# Grove-Barometer_High-Accuracy_v1_0.net
KiCad netlist of a schematic drawn in EAGLE
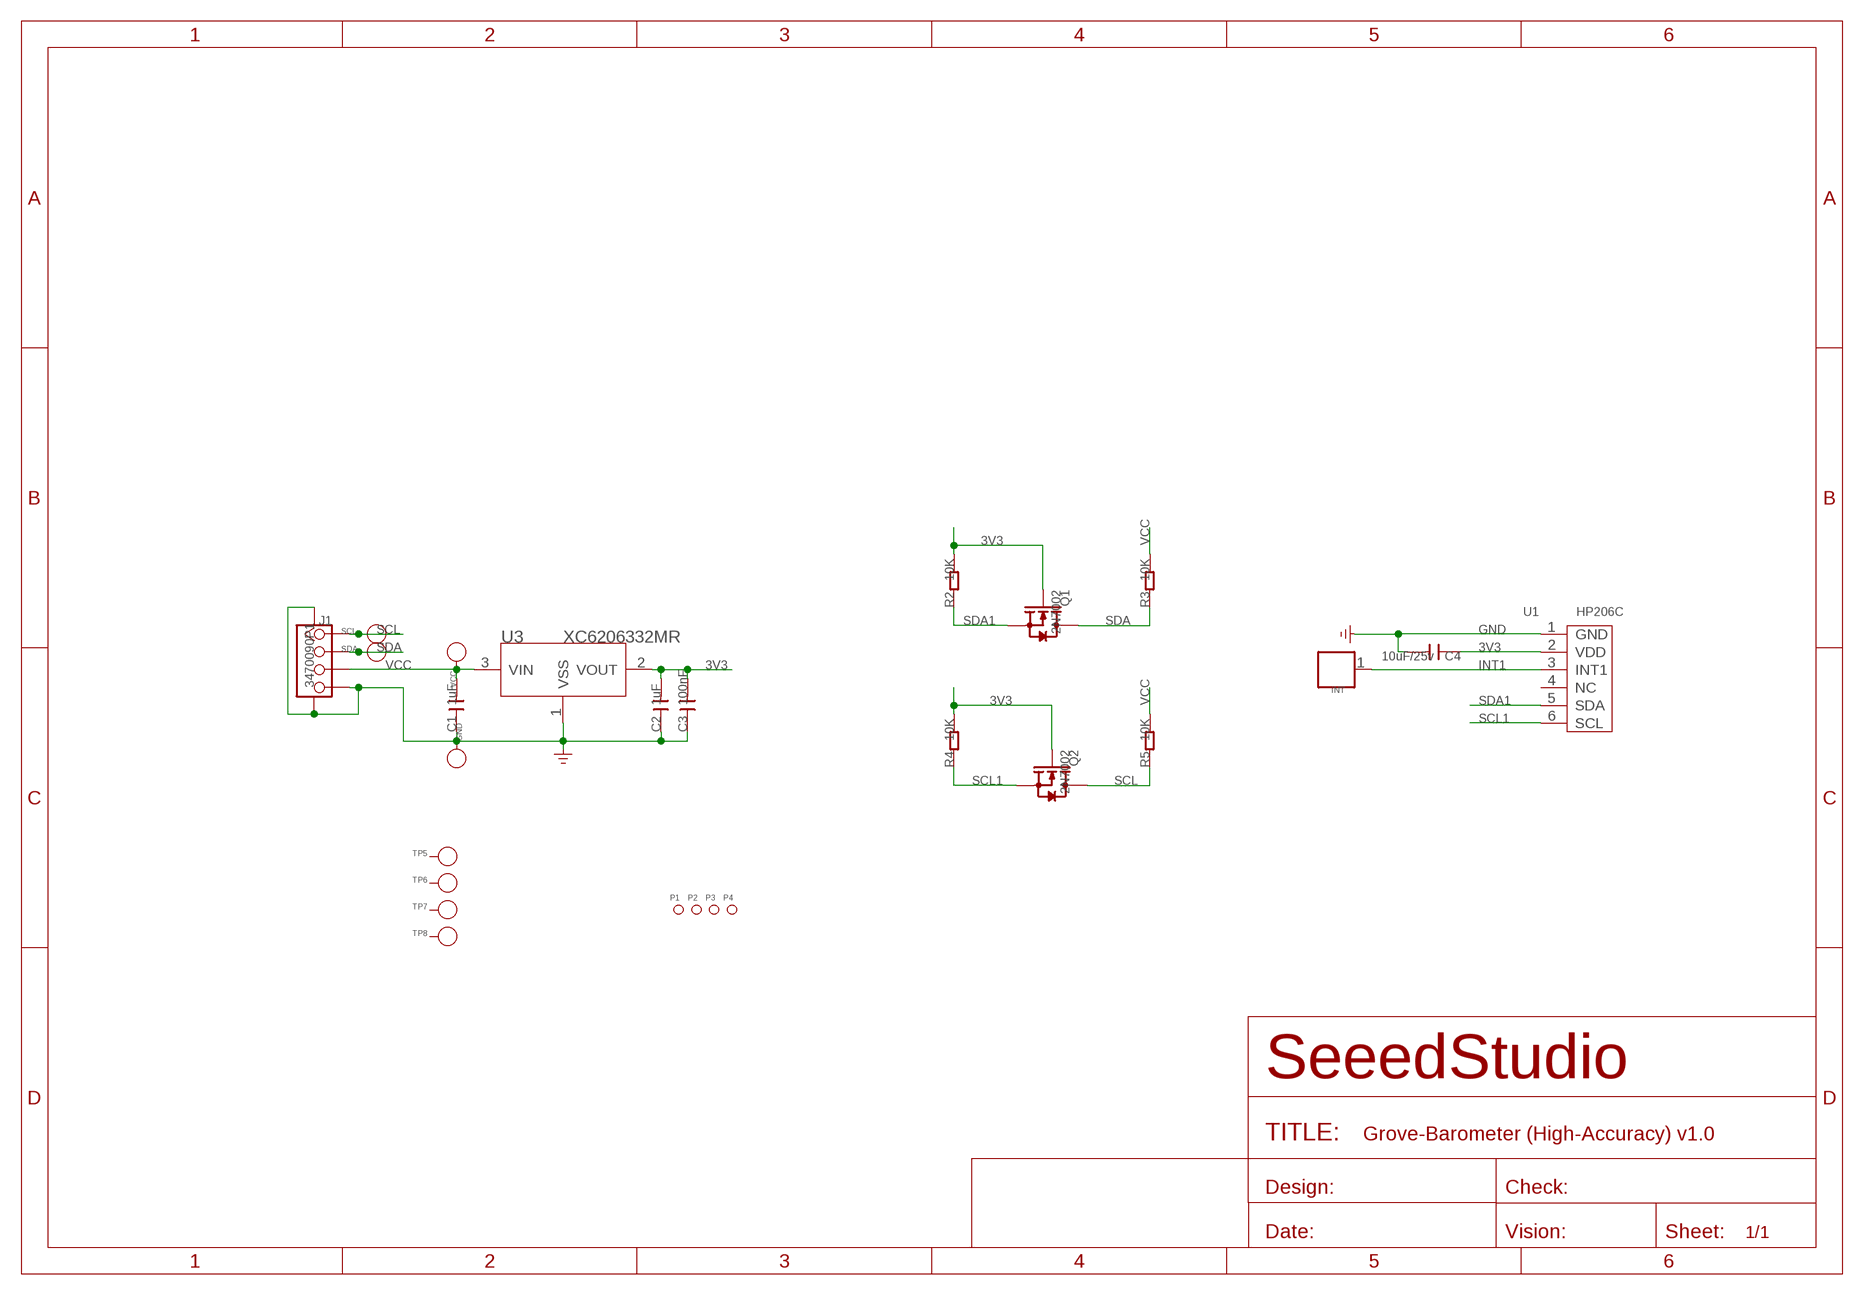
[diagram p0: schematic, sheet 1]

(export (version "E")
  (design (tool "Eeschema 10.0.6"))
  (components
    (comp (ref "C1")
      (value "1uF")
      (footprint "eagle-import:C0603")
      (libsource (lib "eagle-import") (part "C-0603"))
    )
    (comp (ref "C2")
      (value "1uF")
      (footprint "eagle-import:C0603")
      (libsource (lib "eagle-import") (part "C-0603"))
    )
    (comp (ref "C3")
      (value "100nF")
      (footprint "eagle-import:C0603")
      (libsource (lib "eagle-import") (part "C-0603"))
    )
    (comp (ref "C4")
      (value "10uF/25v")
      (footprint "eagle-import:C0805")
      (libsource (lib "eagle-import") (part "C-0805"))
    )
    (comp (ref "GND")
      (value "PAD-TEST-POINT'4545'")
      (footprint "eagle-import:TP_4545")
      (fields (field (name "PARTNO") "DNP"))
      (libsource (lib "eagle-import") (part "PAD-TEST-POINT'4545'"))
    )
    (comp (ref "INT")
      (value "PAD'60/30'")
      (footprint "eagle-import:1P-65_35MIL")
      (libsource (lib "eagle-import") (part "PAD'60/30'"))
    )
    (comp (ref "J1")
      (value "3470090P1")
      (footprint "eagle-import:4P-SMD-2.0")
      (libsource (lib "eagle-import") (part "TWIG-4P-2.0-SMD-FEMALE-REINFORCE'DD'"))
    )
    (comp (ref "P1")
      (value "PAD-MARK")
      (footprint "eagle-import:ROUND-MARK-1.0")
      (fields (field (name "PARTNO") "DNP"))
      (libsource (lib "eagle-import") (part "PAD-MARK"))
    )
    (comp (ref "P2")
      (value "PAD-MARK")
      (footprint "eagle-import:ROUND-MARK-1.0")
      (fields (field (name "PARTNO") "DNP"))
      (libsource (lib "eagle-import") (part "PAD-MARK"))
    )
    (comp (ref "P3")
      (value "PAD-MARK")
      (footprint "eagle-import:ROUND-MARK-1.0")
      (fields (field (name "PARTNO") "DNP"))
      (libsource (lib "eagle-import") (part "PAD-MARK"))
    )
    (comp (ref "P4")
      (value "PAD-MARK")
      (footprint "eagle-import:ROUND-MARK-1.0")
      (fields (field (name "PARTNO") "DNP"))
      (libsource (lib "eagle-import") (part "PAD-MARK"))
    )
    (comp (ref "Q1")
      (value "2N7002")
      (footprint "eagle-import:SOT23")
      (libsource (lib "eagle-import") (part "MOSFET-N'SOT23'"))
    )
    (comp (ref "Q2")
      (value "2N7002")
      (footprint "eagle-import:SOT23")
      (libsource (lib "eagle-import") (part "MOSFET-N'SOT23'"))
    )
    (comp (ref "R2")
      (value "10K")
      (footprint "eagle-import:R0603")
      (libsource (lib "eagle-import") (part "R-0603"))
    )
    (comp (ref "R3")
      (value "10K")
      (footprint "eagle-import:R0603")
      (libsource (lib "eagle-import") (part "R-0603"))
    )
    (comp (ref "R4")
      (value "10K")
      (footprint "eagle-import:R0603")
      (libsource (lib "eagle-import") (part "R-0603"))
    )
    (comp (ref "R5")
      (value "10K")
      (footprint "eagle-import:R0603")
      (libsource (lib "eagle-import") (part "R-0603"))
    )
    (comp (ref "SCL")
      (value "PAD-TEST-POINT'4545'")
      (footprint "eagle-import:TP_4545")
      (fields (field (name "PARTNO") "DNP"))
      (libsource (lib "eagle-import") (part "PAD-TEST-POINT'4545'"))
    )
    (comp (ref "SDA")
      (value "PAD-TEST-POINT'4545'")
      (footprint "eagle-import:TP_4545")
      (fields (field (name "PARTNO") "DNP"))
      (libsource (lib "eagle-import") (part "PAD-TEST-POINT'4545'"))
    )
    (comp (ref "TP5")
      (value "PAD-TEST-POINT'4545'")
      (footprint "eagle-import:TP_4545")
      (fields (field (name "PARTNO") "DNP"))
      (libsource (lib "eagle-import") (part "PAD-TEST-POINT'4545'"))
    )
    (comp (ref "TP6")
      (value "PAD-TEST-POINT'4545'")
      (footprint "eagle-import:TP_4545")
      (fields (field (name "PARTNO") "DNP"))
      (libsource (lib "eagle-import") (part "PAD-TEST-POINT'4545'"))
    )
    (comp (ref "TP7")
      (value "PAD-TEST-POINT'4545'")
      (footprint "eagle-import:TP_4545")
      (fields (field (name "PARTNO") "DNP"))
      (libsource (lib "eagle-import") (part "PAD-TEST-POINT'4545'"))
    )
    (comp (ref "TP8")
      (value "PAD-TEST-POINT'4545'")
      (footprint "eagle-import:TP_4545")
      (fields (field (name "PARTNO") "DNP"))
      (libsource (lib "eagle-import") (part "PAD-TEST-POINT'4545'"))
    )
    (comp (ref "U1")
      (value "HP206C")
      (footprint "eagle-import:6P-SMD-6.8X6.2")
      (libsource (lib "eagle-import") (part "HP206C"))
    )
    (comp (ref "U3")
      (value "XC6206332MR")
      (footprint "eagle-import:SOT23")
      (libsource (lib "eagle-import") (part "XC6206MR"))
    )
    (comp (ref "VCC")
      (value "PAD-TEST-POINT'4545'")
      (footprint "eagle-import:TP_4545")
      (fields (field (name "PARTNO") "DNP"))
      (libsource (lib "eagle-import") (part "PAD-TEST-POINT'4545'"))
    )
  )
  (nets
    (net (code "1") (name "/3V3") (class "Default")
      (node (ref "C2") (pin "2") (pinfunction "2_2") (pintype "passive"))
      (node (ref "C3") (pin "2") (pinfunction "2_2") (pintype "passive"))
      (node (ref "C4") (pin "1") (pinfunction "1_1") (pintype "passive"))
      (node (ref "Q1") (pin "1") (pinfunction "G_1") (pintype "passive"))
      (node (ref "Q2") (pin "1") (pinfunction "G_1") (pintype "passive"))
      (node (ref "R2") (pin "2") (pinfunction "2_2") (pintype "passive"))
      (node (ref "R4") (pin "2") (pinfunction "2_2") (pintype "passive"))
      (node (ref "U1") (pin "2") (pinfunction "VDD_2") (pintype "bidirectional"))
      (node (ref "U3") (pin "2") (pinfunction "VOUT_2") (pintype "output"))
    )
    (net (code "2") (name "/INT1") (class "Default")
      (node (ref "INT") (pin "1") (pinfunction "P$1_1") (pintype "bidirectional"))
      (node (ref "U1") (pin "3") (pinfunction "INT1_3") (pintype "bidirectional"))
    )
    (net (code "3") (name "/SCL") (class "Default")
      (node (ref "J1") (pin "1") (pinfunction "1_1") (pintype "bidirectional"))
      (node (ref "Q2") (pin "3") (pinfunction "D_3") (pintype "passive"))
      (node (ref "R5") (pin "1") (pinfunction "1_1") (pintype "passive"))
      (node (ref "SCL") (pin "T") (pinfunction "T_T") (pintype "bidirectional"))
    )
    (net (code "4") (name "/SCL1") (class "Default")
      (node (ref "Q2") (pin "2") (pinfunction "S_2") (pintype "passive"))
      (node (ref "R4") (pin "1") (pinfunction "1_1") (pintype "passive"))
      (node (ref "U1") (pin "6") (pinfunction "SCL_6") (pintype "bidirectional"))
    )
    (net (code "5") (name "/SDA") (class "Default")
      (node (ref "J1") (pin "2") (pinfunction "2_2") (pintype "bidirectional"))
      (node (ref "Q1") (pin "3") (pinfunction "D_3") (pintype "passive"))
      (node (ref "R3") (pin "1") (pinfunction "1_1") (pintype "passive"))
      (node (ref "SDA") (pin "T") (pinfunction "T_T") (pintype "bidirectional"))
    )
    (net (code "6") (name "/SDA1") (class "Default")
      (node (ref "Q1") (pin "2") (pinfunction "S_2") (pintype "passive"))
      (node (ref "R2") (pin "1") (pinfunction "1_1") (pintype "passive"))
      (node (ref "U1") (pin "5") (pinfunction "SDA_5") (pintype "bidirectional"))
    )
    (net (code "7") (name "/VCC") (class "Default")
      (node (ref "C1") (pin "2") (pinfunction "2_2") (pintype "passive"))
      (node (ref "J1") (pin "3") (pinfunction "3_3") (pintype "bidirectional"))
      (node (ref "R3") (pin "2") (pinfunction "2_2") (pintype "passive"))
      (node (ref "R5") (pin "2") (pinfunction "2_2") (pintype "passive"))
      (node (ref "U3") (pin "3") (pinfunction "VIN_3") (pintype "input"))
      (node (ref "VCC") (pin "T") (pinfunction "T_T") (pintype "bidirectional"))
    )
    (net (code "8") (name "GND_POWER") (class "Default")
      (node (ref "C1") (pin "1") (pinfunction "1_1") (pintype "passive"))
      (node (ref "C2") (pin "1") (pinfunction "1_1") (pintype "passive"))
      (node (ref "C3") (pin "1") (pinfunction "1_1") (pintype "passive"))
      (node (ref "C4") (pin "2") (pinfunction "2_2") (pintype "passive"))
      (node (ref "GND") (pin "T") (pinfunction "T_T") (pintype "bidirectional"))
      (node (ref "J1") (pin "4") (pinfunction "4_4") (pintype "bidirectional"))
      (node (ref "J1") (pin "SS1") (pinfunction "SS1_SS1") (pintype "bidirectional"))
      (node (ref "J1") (pin "SS2") (pinfunction "SS2_SS2") (pintype "bidirectional"))
      (node (ref "U1") (pin "1") (pinfunction "GND_1") (pintype "bidirectional"))
      (node (ref "U3") (pin "1") (pinfunction "VSS_1") (pintype "power_in"))
    )
    (net (code "9") (name "unconnected-(TP5-PadT)") (class "Default")
      (node (ref "TP5") (pin "T") (pinfunction "T_T") (pintype "bidirectional"))
    )
    (net (code "10") (name "unconnected-(TP6-PadT)") (class "Default")
      (node (ref "TP6") (pin "T") (pinfunction "T_T") (pintype "bidirectional"))
    )
    (net (code "11") (name "unconnected-(TP7-PadT)") (class "Default")
      (node (ref "TP7") (pin "T") (pinfunction "T_T") (pintype "bidirectional"))
    )
    (net (code "12") (name "unconnected-(TP8-PadT)") (class "Default")
      (node (ref "TP8") (pin "T") (pinfunction "T_T") (pintype "bidirectional"))
    )
    (net (code "13") (name "unconnected-(U1-NC-Pad4)") (class "Default")
      (node (ref "U1") (pin "4") (pinfunction "NC_4") (pintype "bidirectional"))
    )
  )
)
